# Sheet2.net
KiCad netlist of a schematic drawn in Altium Designer
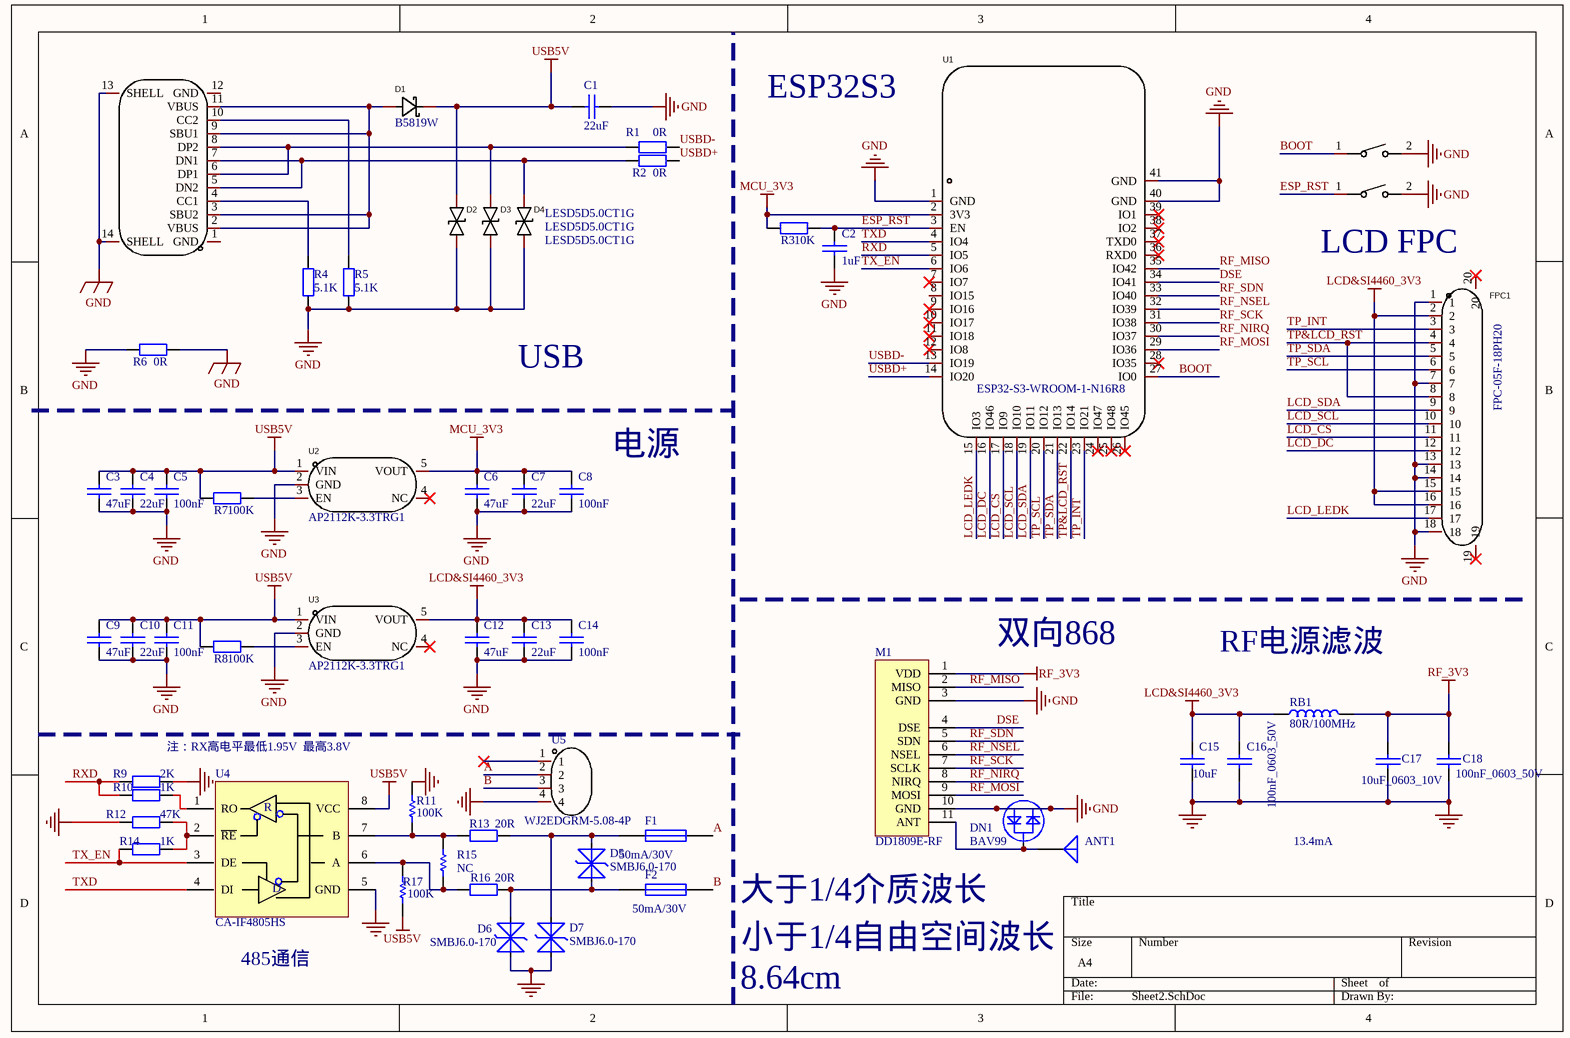
[diagram p0: Sheet2.SchDoc]

(export (version "E")
  (design (tool "Eeschema 10.0.6"))
  (components
    (comp (ref "ANT1")
      (value "~")
      (footprint "18AWG")
      (description "Generic Antenna")
      (fields (field (name "PUBLISHER") "Altium Limited"))
      (libsource (lib "原理图库") (part "Antenna"))
    )
    (comp (ref "C1")
      (value "22uF")
      (footprint "0603_C")
      (description "贴片电容")
      (libsource (lib "Schlib1") (part "CAP_SMT"))
    )
    (comp (ref "C2")
      (value "1uF")
      (footprint "0603_C")
      (description "贴片电容")
      (libsource (lib "Schlib1") (part "CAP_SMT"))
    )
    (comp (ref "C3")
      (value "47uF")
      (footprint "0603_C")
      (description "贴片电容")
      (libsource (lib "Schlib1") (part "CAP_SMT"))
    )
    (comp (ref "C4")
      (value "22uF")
      (footprint "0603_C")
      (description "贴片电容")
      (libsource (lib "Schlib1") (part "CAP_SMT"))
    )
    (comp (ref "C5")
      (value "100nF")
      (footprint "0603_C")
      (description "贴片电容")
      (libsource (lib "Schlib1") (part "CAP_SMT"))
    )
    (comp (ref "C6")
      (value "47uF")
      (footprint "0603_C")
      (description "贴片电容")
      (libsource (lib "Schlib1") (part "CAP_SMT"))
    )
    (comp (ref "C7")
      (value "22uF")
      (footprint "0603_C")
      (description "贴片电容")
      (libsource (lib "Schlib1") (part "CAP_SMT"))
    )
    (comp (ref "C8")
      (value "100nF")
      (footprint "0603_C")
      (description "贴片电容")
      (libsource (lib "Schlib1") (part "CAP_SMT"))
    )
    (comp (ref "C9")
      (value "47uF")
      (footprint "0603_C")
      (description "贴片电容")
      (libsource (lib "Schlib1") (part "CAP_SMT"))
    )
    (comp (ref "C10")
      (value "22uF")
      (footprint "0603_C")
      (description "贴片电容")
      (libsource (lib "Schlib1") (part "CAP_SMT"))
    )
    (comp (ref "C11")
      (value "100nF")
      (footprint "0603_C")
      (description "贴片电容")
      (libsource (lib "Schlib1") (part "CAP_SMT"))
    )
    (comp (ref "C12")
      (value "47uF")
      (footprint "0603_C")
      (description "贴片电容")
      (libsource (lib "Schlib1") (part "CAP_SMT"))
    )
    (comp (ref "C13")
      (value "22uF")
      (footprint "0603_C")
      (description "贴片电容")
      (libsource (lib "Schlib1") (part "CAP_SMT"))
    )
    (comp (ref "C14")
      (value "100nF")
      (footprint "0603_C")
      (description "贴片电容")
      (libsource (lib "Schlib1") (part "CAP_SMT"))
    )
    (comp (ref "C15")
      (value "10uF")
      (footprint "0603_C")
      (description "瓷片电容 X5R-0603-10V-10uF/C-±10%")
      (fields (field (name "Comment") "10uF_0603_10V"))
      (libsource (lib "mine") (part "10uF_0603_10V"))
    )
    (comp (ref "C16")
      (value "100nF_0603_50V")
      (footprint "0603_C")
      (description "电容 瓷片 X7R-0603-50V-0.1uF/C-±10%")
      (libsource (lib "mine") (part "100nF_0603_50V"))
    )
    (comp (ref "C17")
      (value "10uF_0603_10V")
      (footprint "0603_C")
      (description "瓷片电容 X5R-0603-10V-10uF/C-±10%")
      (libsource (lib "mine") (part "10uF_0603_10V"))
    )
    (comp (ref "C18")
      (value "100nF_0603_50V")
      (footprint "0603_C")
      (description "电容 瓷片 X7R-0603-50V-0.1uF/C-±10%")
      (libsource (lib "mine") (part "100nF_0603_50V"))
    )
    (comp (ref "D1")
      (value "B5819W")
      (footprint "SOD-123F_L2.7-W1.6-LS3.8-RD-1")
      (fields (field (name "MANUFACTURER") "GOODWORK(固得沃克)"))
      (libsource (lib "Schlib1") (part "B5819W"))
    )
    (comp (ref "D2")
      (value "LESD5D5.0CT1G")
      (footprint "SOD-523_L1.2-W0.8-LS1.6-BI")
      (fields (field (name "MANUFACTURER") "LRC(乐山无线电)"))
      (libsource (lib "Schlib1") (part "LESD5D5.0CT1G"))
    )
    (comp (ref "D3")
      (value "LESD5D5.0CT1G")
      (footprint "SOD-523_L1.2-W0.8-LS1.6-BI")
      (fields (field (name "MANUFACTURER") "LRC(乐山无线电)"))
      (libsource (lib "Schlib1") (part "LESD5D5.0CT1G"))
    )
    (comp (ref "D4")
      (value "LESD5D5.0CT1G")
      (footprint "SOD-523_L1.2-W0.8-LS1.6-BI")
      (fields (field (name "MANUFACTURER") "LRC(乐山无线电)"))
      (libsource (lib "Schlib1") (part "LESD5D5.0CT1G"))
    )
    (comp (ref "D5")
      (value "SMBJ6.0-170")
      (footprint "SMB(DO-214AA) - TVS")
      (description "TVS")
      (libsource (lib "Schlib1") (part "TVS"))
    )
    (comp (ref "D6")
      (value "SMBJ6.0-170")
      (footprint "SMB(DO-214AA) - TVS")
      (description "TVS")
      (libsource (lib "Schlib1") (part "TVS"))
    )
    (comp (ref "D7")
      (value "SMBJ6.0-170")
      (footprint "SMB(DO-214AA) - TVS")
      (description "TVS")
      (libsource (lib "Schlib1") (part "TVS"))
    )
    (comp (ref "DN1") (value "BAV99") (footprint "SOT-23(SOT-23-3)") (libsource (lib "Ruan") (part "BAV99")))
    (comp (ref "F1")
      (value "贴片自恢复保险丝 1812 0.1A 60V")
      (footprint "1206_R")
      (description "Fuse")
      (fields (field (name "ALTIUM_UNNAMED_1") "50mA/30V") (field (name "PUBLISHER") "Altium Limited"))
      (libsource (lib "*") (part "Fuse 1"))
    )
    (comp (ref "F2")
      (value "贴片自恢复保险丝 1812 0.1A 60V")
      (footprint "1206_R")
      (description "Fuse")
      (fields (field (name "ALTIUM_UNNAMED_1") "50mA/30V") (field (name "PUBLISHER") "Altium Limited"))
      (libsource (lib "*") (part "Fuse 1"))
    )
    (comp (ref "FPC1")
      (value "FPC-05F-18PH20")
      (footprint "FPC-SMD_18P-P0.50_FPC-05F-18PH20")
      (fields (field (name "MANUFACTURER") "XUNPU(讯普)"))
      (libsource (lib "Schlib1") (part "FPC-05F-18PH20"))
    )
    (comp (ref "M1")
      (value "DD1809E-RF")
      (footprint "DD1809(E)-RF-平")
      (description "平插")
      (libsource (lib "Ruan") (part "DD1809E-RF"))
    )
    (comp (ref "R1")
      (value "0R")
      (footprint "0603_R")
      (description "Resistor")
      (fields (field (name "PUBLISHER") "Altium Limited"))
      (libsource (lib "Schlib1") (part "RES"))
    )
    (comp (ref "R2")
      (value "0R")
      (footprint "0603_R")
      (description "Resistor")
      (fields (field (name "PUBLISHER") "Altium Limited"))
      (libsource (lib "Schlib1") (part "RES"))
    )
    (comp (ref "R3")
      (value "10K")
      (footprint "0603_R")
      (description "Resistor")
      (fields (field (name "Comment") "0R") (field (name "PUBLISHER") "Altium Limited"))
      (libsource (lib "Schlib1") (part "RES"))
    )
    (comp (ref "R4")
      (value "5.1K")
      (footprint "0603_R")
      (description "Resistor")
      (fields (field (name "PUBLISHER") "Altium Limited"))
      (libsource (lib "") (part "RES_1"))
    )
    (comp (ref "R5")
      (value "5.1K")
      (footprint "0603_R")
      (description "Resistor")
      (fields (field (name "PUBLISHER") "Altium Limited"))
      (libsource (lib "") (part "RES_1"))
    )
    (comp (ref "R6")
      (value "0R")
      (footprint "0603_R")
      (description "Resistor")
      (fields (field (name "PUBLISHER") "Altium Limited"))
      (libsource (lib "Schlib1") (part "RES"))
    )
    (comp (ref "R7")
      (value "100K")
      (footprint "0603_R")
      (description "Resistor")
      (fields (field (name "PUBLISHER") "Altium Limited"))
      (libsource (lib "Schlib1") (part "RES"))
    )
    (comp (ref "R8")
      (value "100K")
      (footprint "0603_R")
      (description "Resistor")
      (fields (field (name "PUBLISHER") "Altium Limited"))
      (libsource (lib "Schlib1") (part "RES"))
    )
    (comp (ref "R9")
      (value "2K")
      (footprint "0603_R")
      (description "Resistor")
      (fields (field (name "PUBLISHER") "Altium Limited"))
      (libsource (lib "") (part "Res2_2"))
    )
    (comp (ref "R10")
      (value "1K")
      (footprint "0603_R")
      (description "Resistor")
      (fields (field (name "PUBLISHER") "Altium Limited"))
      (libsource (lib "") (part "Res2_1"))
    )
    (comp (ref "R11")
      (value "100K")
      (footprint "0603_R")
      (description "Resistor")
      (fields (field (name "PUBLISHER") "Altium Limited"))
      (libsource (lib "*") (part "Res1"))
    )
    (comp (ref "R12")
      (value "47K")
      (footprint "0603_R")
      (description "Resistor")
      (fields (field (name "PUBLISHER") "Altium Limited"))
      (libsource (lib "") (part "Res2_1"))
    )
    (comp (ref "R13")
      (value "20R")
      (footprint "0603_R")
      (description "Resistor")
      (fields (field (name "PUBLISHER") "Altium Limited"))
      (libsource (lib "*") (part "Res2"))
    )
    (comp (ref "R14")
      (value "1K")
      (footprint "0603_R")
      (description "Resistor")
      (fields (field (name "PUBLISHER") "Altium Limited"))
      (libsource (lib "") (part "Res2_1"))
    )
    (comp (ref "R15")
      (value "NC")
      (footprint "0603_R")
      (description "Resistor")
      (fields (field (name "PUBLISHER") "Altium Limited"))
      (libsource (lib "*") (part "Res1"))
    )
    (comp (ref "R16")
      (value "20R")
      (footprint "0603_R")
      (description "Resistor")
      (fields (field (name "PUBLISHER") "Altium Limited"))
      (libsource (lib "*") (part "Res2"))
    )
    (comp (ref "R17")
      (value "100K")
      (footprint "0603_R")
      (description "Resistor")
      (fields (field (name "PUBLISHER") "Altium Limited"))
      (libsource (lib "*") (part "Res1"))
    )
    (comp (ref "RB1")
      (value "80R/100MHz")
      (footprint "0603_R")
      (description "磁珠 80R/100MHZ 贴片0603")
      (fields (field (name "Comment") "80R/100MHz_0603"))
      (libsource (lib "mine") (part "80R/100MHz_0603"))
    )
    (comp (ref "SW1")
      (value "TS-1088-AR02016")
      (footprint "SW-SMD_L3.9-W3.0-P4.45")
      (fields (field (name "MANUFACTURER") "XUNPU(讯普)"))
      (libsource (lib "Schlib1") (part "KEY"))
    )
    (comp (ref "SW2")
      (value "TS-1088-AR02016")
      (footprint "SW-SMD_L3.9-W3.0-P4.45")
      (fields (field (name "MANUFACTURER") "XUNPU(讯普)"))
      (libsource (lib "Schlib1") (part "KEY"))
    )
    (comp (ref "U1")
      (value "ESP32-S3-WROOM-1-N16R8")
      (footprint "WIRELM-SMD_ESP32-S3-WROOM-1")
      (fields (field (name "MANUFACTURER") "ESPRESSIF(乐鑫)"))
      (libsource (lib "Schlib1") (part "ESP32-S3-WROOM-1-N16R8"))
    )
    (comp (ref "U2")
      (value "AP2112K-3.3TRG1")
      (footprint "SOT-25-5_L2.9-W1.6-P0.95-LS2.8-BL")
      (fields (field (name "MANUFACTURER") "DIODES(美台)"))
      (libsource (lib "Schlib1") (part "AP2112K-3.3TRG1"))
    )
    (comp (ref "U3")
      (value "AP2112K-3.3TRG1")
      (footprint "SOT-25-5_L2.9-W1.6-P0.95-LS2.8-BL")
      (fields (field (name "MANUFACTURER") "DIODES(美台)"))
      (libsource (lib "Schlib1") (part "AP2112K-3.3TRG1"))
    )
    (comp (ref "U4")
      (value "CA-IF4805HS")
      (footprint "SOP8")
      (description "MAX485E")
      (libsource (lib "N IC-GRC") (part "MAX485E"))
    )
    (comp (ref "U5")
      (value "WJ2EDGRM-5.08-4P")
      (footprint "CONN-TH_4P-P5.08_WJ2EDGRM-5.08-4P-14-00A")
      (description "连接器类型:板端/插座-闭口;间距:5.08mm;排数:1;每排PIN数:4;安装方式:弯针;颜色:绿色;固定方式:螺丝固定;")
      (fields (field (name "MANUFACTURER") "KANGNEX(康奈克斯电气)") (field (name "NAME") "WJ2EDGRM-5.08-4P"))
      (libsource (lib "Schlib1") (part "WJ2EDGRM-5.08-4P"))
    )
    (comp (ref "USB1")
      (value "TYPE-C 16PIN 2MD(073)")
      (footprint "USB-C-SMD_TYPE-C-6PIN-2MD-073")
      (fields (field (name "MANUFACTURER") "SHOU HAN(首韩)"))
      (libsource (lib "Schlib1") (part "TYPE-C 16PIN 2MD(073)"))
    )
  )
  (nets
    (net (code "1") (name "/A") (class "Default")
      (node (ref "F1") (pin "2") (pinfunction "2_2") (pintype "passive"))
      (node (ref "U5") (pin "2") (pinfunction "2_2") (pintype "passive"))
    )
    (net (code "2") (name "/B") (class "Default")
      (node (ref "F2") (pin "2") (pinfunction "2_2") (pintype "passive"))
      (node (ref "U5") (pin "3") (pinfunction "3_3") (pintype "passive"))
    )
    (net (code "3") (name "/BOOT") (class "Default")
      (node (ref "SW1") (pin "1") (pinfunction "1_1") (pintype "passive"))
      (node (ref "U1") (pin "27") (pinfunction "IO0_27") (pintype "passive"))
    )
    (net (code "4") (name "/DSE") (class "Default")
      (node (ref "M1") (pin "4") (pinfunction "DSE_4") (pintype "passive"))
      (node (ref "U1") (pin "34") (pinfunction "IO41_34") (pintype "passive"))
    )
    (net (code "5") (name "/ESP_RST") (class "Default")
      (node (ref "C2") (pin "2") (pinfunction "2_2") (pintype "passive"))
      (node (ref "R3") (pin "2") (pinfunction "2_2") (pintype "passive"))
      (node (ref "SW2") (pin "1") (pinfunction "1_1") (pintype "passive"))
      (node (ref "U1") (pin "3") (pinfunction "EN_3") (pintype "passive"))
    )
    (net (code "6") (name "/LCD_CS") (class "Default")
      (node (ref "FPC1") (pin "11") (pinfunction "11_11") (pintype "passive"))
      (node (ref "U1") (pin "17") (pinfunction "IO9_17") (pintype "passive"))
    )
    (net (code "7") (name "/LCD_DC") (class "Default")
      (node (ref "FPC1") (pin "12") (pinfunction "12_12") (pintype "passive"))
      (node (ref "U1") (pin "16") (pinfunction "IO46_16") (pintype "passive"))
    )
    (net (code "8") (name "/LCD_LEDK") (class "Default")
      (node (ref "FPC1") (pin "17") (pinfunction "17_17") (pintype "passive"))
      (node (ref "U1") (pin "15") (pinfunction "IO3_15") (pintype "passive"))
    )
    (net (code "9") (name "/LCD_SCL") (class "Default")
      (node (ref "FPC1") (pin "10") (pinfunction "10_10") (pintype "passive"))
      (node (ref "U1") (pin "18") (pinfunction "IO10_18") (pintype "passive"))
    )
    (net (code "10") (name "/LCD_SDA") (class "Default")
      (node (ref "FPC1") (pin "9") (pinfunction "9_9") (pintype "passive"))
      (node (ref "U1") (pin "19") (pinfunction "IO11_19") (pintype "passive"))
    )
    (net (code "11") (name "/RF_MISO") (class "Default")
      (node (ref "M1") (pin "2") (pinfunction "MISO_2") (pintype "passive"))
      (node (ref "U1") (pin "35") (pinfunction "IO42_35") (pintype "passive"))
    )
    (net (code "12") (name "/RF_MOSI") (class "Default")
      (node (ref "M1") (pin "9") (pinfunction "MOSI_9") (pintype "passive"))
      (node (ref "U1") (pin "29") (pinfunction "IO36_29") (pintype "passive"))
    )
    (net (code "13") (name "/RF_NIRQ") (class "Default")
      (node (ref "M1") (pin "8") (pinfunction "NIRQ_8") (pintype "passive"))
      (node (ref "U1") (pin "30") (pinfunction "IO37_30") (pintype "passive"))
    )
    (net (code "14") (name "/RF_NSEL") (class "Default")
      (node (ref "M1") (pin "6") (pinfunction "NSEL_6") (pintype "passive"))
      (node (ref "U1") (pin "32") (pinfunction "IO39_32") (pintype "passive"))
    )
    (net (code "15") (name "/RF_SCK") (class "Default")
      (node (ref "M1") (pin "7") (pinfunction "SCLK_7") (pintype "passive"))
      (node (ref "U1") (pin "31") (pinfunction "IO38_31") (pintype "passive"))
    )
    (net (code "16") (name "/RF_SDN") (class "Default")
      (node (ref "M1") (pin "5") (pinfunction "SDN_5") (pintype "passive"))
      (node (ref "U1") (pin "33") (pinfunction "IO40_33") (pintype "passive"))
    )
    (net (code "17") (name "/RXD") (class "Default")
      (node (ref "R10") (pin "1") (pinfunction "1_1") (pintype "passive"))
      (node (ref "R9") (pin "2") (pinfunction "2_2") (pintype "passive"))
      (node (ref "U1") (pin "5") (pinfunction "IO5_5") (pintype "passive"))
    )
    (net (code "18") (name "/TP&LCD_RST") (class "Default")
      (node (ref "FPC1") (pin "4") (pinfunction "4_4") (pintype "passive"))
      (node (ref "FPC1") (pin "8") (pinfunction "8_8") (pintype "passive"))
      (node (ref "U1") (pin "22") (pinfunction "IO14_22") (pintype "passive"))
    )
    (net (code "19") (name "/TP_INT") (class "Default")
      (node (ref "FPC1") (pin "3") (pinfunction "3_3") (pintype "passive"))
      (node (ref "U1") (pin "23") (pinfunction "IO21_23") (pintype "passive"))
    )
    (net (code "20") (name "/TP_SCL") (class "Default")
      (node (ref "FPC1") (pin "6") (pinfunction "6_6") (pintype "passive"))
      (node (ref "U1") (pin "20") (pinfunction "IO12_20") (pintype "passive"))
    )
    (net (code "21") (name "/TP_SDA") (class "Default")
      (node (ref "FPC1") (pin "5") (pinfunction "5_5") (pintype "passive"))
      (node (ref "U1") (pin "21") (pinfunction "IO13_21") (pintype "passive"))
    )
    (net (code "22") (name "/TXD") (class "Default")
      (node (ref "U1") (pin "4") (pinfunction "IO4_4") (pintype "passive"))
      (node (ref "U4") (pin "4") (pinfunction "DI_4") (pintype "passive"))
    )
    (net (code "23") (name "/TX_EN") (class "Default")
      (node (ref "R14") (pin "1") (pinfunction "1_1") (pintype "passive"))
      (node (ref "U1") (pin "6") (pinfunction "IO6_6") (pintype "passive"))
      (node (ref "U4") (pin "3") (pinfunction "DE_3") (pintype "passive"))
    )
    (net (code "24") (name "/USBD+") (class "Default")
      (node (ref "R2") (pin "2") (pinfunction "2_2") (pintype "passive"))
      (node (ref "U1") (pin "14") (pinfunction "IO20_14") (pintype "passive"))
    )
    (net (code "25") (name "/USBD-") (class "Default")
      (node (ref "R1") (pin "2") (pinfunction "2_2") (pintype "passive"))
      (node (ref "U1") (pin "13") (pinfunction "IO19_13") (pintype "passive"))
    )
    (net (code "26") (name "GND") (class "Default")
      (node (ref "C1") (pin "2") (pinfunction "2_2") (pintype "passive"))
      (node (ref "C10") (pin "1") (pinfunction "1_1") (pintype "passive"))
      (node (ref "C11") (pin "1") (pinfunction "1_1") (pintype "passive"))
      (node (ref "C12") (pin "1") (pinfunction "1_1") (pintype "passive"))
      (node (ref "C13") (pin "1") (pinfunction "1_1") (pintype "passive"))
      (node (ref "C14") (pin "1") (pinfunction "1_1") (pintype "passive"))
      (node (ref "C15") (pin "2") (pinfunction "2_2") (pintype "passive"))
      (node (ref "C16") (pin "1") (pinfunction "1_1") (pintype "passive"))
      (node (ref "C17") (pin "1") (pinfunction "1_1") (pintype "passive"))
      (node (ref "C18") (pin "1") (pinfunction "1_1") (pintype "passive"))
      (node (ref "C2") (pin "1") (pinfunction "1_1") (pintype "passive"))
      (node (ref "C3") (pin "1") (pinfunction "1_1") (pintype "passive"))
      (node (ref "C4") (pin "1") (pinfunction "1_1") (pintype "passive"))
      (node (ref "C5") (pin "1") (pinfunction "1_1") (pintype "passive"))
      (node (ref "C6") (pin "1") (pinfunction "1_1") (pintype "passive"))
      (node (ref "C7") (pin "1") (pinfunction "1_1") (pintype "passive"))
      (node (ref "C8") (pin "1") (pinfunction "1_1") (pintype "passive"))
      (node (ref "C9") (pin "1") (pinfunction "1_1") (pintype "passive"))
      (node (ref "D2") (pin "1") (pinfunction "1_1") (pintype "passive"))
      (node (ref "D3") (pin "1") (pinfunction "1_1") (pintype "passive"))
      (node (ref "D4") (pin "1") (pinfunction "1_1") (pintype "passive"))
      (node (ref "D6") (pin "1") (pinfunction "1_1") (pintype "passive"))
      (node (ref "D7") (pin "1") (pinfunction "1_1") (pintype "passive"))
      (node (ref "DN1") (pin "1") (pinfunction "1_1") (pintype "passive"))
      (node (ref "DN1") (pin "2") (pinfunction "2_2") (pintype "passive"))
      (node (ref "FPC1") (pin "1") (pinfunction "1_1") (pintype "passive"))
      (node (ref "FPC1") (pin "13") (pinfunction "13_13") (pintype "passive"))
      (node (ref "FPC1") (pin "14") (pinfunction "14_14") (pintype "passive"))
      (node (ref "FPC1") (pin "18") (pinfunction "18_18") (pintype "passive"))
      (node (ref "FPC1") (pin "7") (pinfunction "7_7") (pintype "passive"))
      (node (ref "M1") (pin "10") (pinfunction "GND_10") (pintype "passive"))
      (node (ref "M1") (pin "3") (pinfunction "GND_3") (pintype "passive"))
      (node (ref "R11") (pin "2") (pinfunction "2_2") (pintype "passive"))
      (node (ref "R12") (pin "1") (pinfunction "1_1") (pintype "passive"))
      (node (ref "R4") (pin "1") (pinfunction "1_1") (pintype "passive"))
      (node (ref "R5") (pin "1") (pinfunction "1_1") (pintype "passive"))
      (node (ref "R6") (pin "1") (pinfunction "1_1") (pintype "passive"))
      (node (ref "R6") (pin "2") (pinfunction "2_2") (pintype "passive"))
      (node (ref "R9") (pin "1") (pinfunction "1_1") (pintype "passive"))
      (node (ref "SW1") (pin "2") (pinfunction "2_2") (pintype "passive"))
      (node (ref "SW2") (pin "2") (pinfunction "2_2") (pintype "passive"))
      (node (ref "U1") (pin "1") (pinfunction "GND_1") (pintype "passive"))
      (node (ref "U1") (pin "40") (pinfunction "GND_40") (pintype "passive"))
      (node (ref "U1") (pin "41") (pinfunction "GND_41") (pintype "passive"))
      (node (ref "U2") (pin "2") (pinfunction "GND_2") (pintype "passive"))
      (node (ref "U3") (pin "2") (pinfunction "GND_2") (pintype "passive"))
      (node (ref "U4") (pin "5") (pinfunction "GND_5") (pintype "passive"))
      (node (ref "U5") (pin "4") (pinfunction "4_4") (pintype "passive"))
      (node (ref "USB1") (pin "13") (pinfunction "SHELL_13") (pintype "passive"))
      (node (ref "USB1") (pin "14") (pinfunction "SHELL_14") (pintype "passive"))
    )
    (net (code "27") (name "LCD&SI4460_3V3") (class "Default")
      (node (ref "C12") (pin "2") (pinfunction "2_2") (pintype "passive"))
      (node (ref "C13") (pin "2") (pinfunction "2_2") (pintype "passive"))
      (node (ref "C14") (pin "2") (pinfunction "2_2") (pintype "passive"))
      (node (ref "C15") (pin "1") (pinfunction "1_1") (pintype "passive"))
      (node (ref "C16") (pin "2") (pinfunction "2_2") (pintype "passive"))
      (node (ref "FPC1") (pin "15") (pinfunction "15_15") (pintype "passive"))
      (node (ref "FPC1") (pin "16") (pinfunction "16_16") (pintype "passive"))
      (node (ref "FPC1") (pin "2") (pinfunction "2_2") (pintype "passive"))
      (node (ref "RB1") (pin "1") (pinfunction "1_1") (pintype "passive"))
      (node (ref "U3") (pin "5") (pinfunction "VOUT_5") (pintype "passive"))
    )
    (net (code "28") (name "MCU_3V3") (class "Default")
      (node (ref "C6") (pin "2") (pinfunction "2_2") (pintype "passive"))
      (node (ref "C7") (pin "2") (pinfunction "2_2") (pintype "passive"))
      (node (ref "C8") (pin "2") (pinfunction "2_2") (pintype "passive"))
      (node (ref "R3") (pin "1") (pinfunction "1_1") (pintype "passive"))
      (node (ref "U1") (pin "2") (pinfunction "3V3_2") (pintype "passive"))
      (node (ref "U2") (pin "5") (pinfunction "VOUT_5") (pintype "passive"))
    )
    (net (code "29") (name "Net-(ANT1-A)") (class "Default")
      (node (ref "ANT1") (pin "1") (pinfunction "A_1") (pintype "passive"))
      (node (ref "DN1") (pin "3") (pinfunction "3_3") (pintype "passive"))
      (node (ref "M1") (pin "11") (pinfunction "ANT_11") (pintype "passive"))
    )
    (net (code "30") (name "Net-(D1-A)") (class "Default")
      (node (ref "D1") (pin "2") (pinfunction "A_2") (pintype "passive"))
      (node (ref "USB1") (pin "11") (pinfunction "VBUS_11") (pintype "passive"))
      (node (ref "USB1") (pin "2") (pinfunction "VBUS_2") (pintype "passive"))
      (node (ref "USB1") (pin "3") (pinfunction "SBU2_3") (pintype "passive"))
      (node (ref "USB1") (pin "9") (pinfunction "SBU1_9") (pintype "passive"))
    )
    (net (code "31") (name "Net-(D5-Pad1)") (class "Default")
      (node (ref "D5") (pin "1") (pinfunction "1_1") (pintype "passive"))
      (node (ref "D6") (pin "2") (pinfunction "2_2") (pintype "passive"))
      (node (ref "F2") (pin "1") (pinfunction "1_1") (pintype "passive"))
      (node (ref "R16") (pin "1") (pinfunction "1_1") (pintype "passive"))
    )
    (net (code "32") (name "Net-(D5-Pad2)") (class "Default")
      (node (ref "D5") (pin "2") (pinfunction "2_2") (pintype "passive"))
      (node (ref "D7") (pin "2") (pinfunction "2_2") (pintype "passive"))
      (node (ref "F1") (pin "1") (pinfunction "1_1") (pintype "passive"))
      (node (ref "R13") (pin "1") (pinfunction "1_1") (pintype "passive"))
    )
    (net (code "33") (name "Net-(U2-EN)") (class "Default")
      (node (ref "R7") (pin "2") (pinfunction "2_2") (pintype "passive"))
      (node (ref "U2") (pin "3") (pinfunction "EN_3") (pintype "passive"))
    )
    (net (code "34") (name "Net-(U3-EN)") (class "Default")
      (node (ref "R8") (pin "2") (pinfunction "2_2") (pintype "passive"))
      (node (ref "U3") (pin "3") (pinfunction "EN_3") (pintype "passive"))
    )
    (net (code "35") (name "Net-(U4-A)") (class "Default")
      (node (ref "R15") (pin "1") (pinfunction "1_1") (pintype "passive"))
      (node (ref "R16") (pin "2") (pinfunction "2_2") (pintype "passive"))
      (node (ref "R17") (pin "2") (pinfunction "2_2") (pintype "passive"))
      (node (ref "U4") (pin "6") (pinfunction "A_6") (pintype "passive"))
    )
    (net (code "36") (name "Net-(U4-B)") (class "Default")
      (node (ref "R11") (pin "1") (pinfunction "1_1") (pintype "passive"))
      (node (ref "R13") (pin "2") (pinfunction "2_2") (pintype "passive"))
      (node (ref "R15") (pin "2") (pinfunction "2_2") (pintype "passive"))
      (node (ref "U4") (pin "7") (pinfunction "B_7") (pintype "passive"))
    )
    (net (code "37") (name "Net-(U4-RO)") (class "Default")
      (node (ref "R10") (pin "2") (pinfunction "2_2") (pintype "passive"))
      (node (ref "U4") (pin "1") (pinfunction "RO_1") (pintype "passive"))
    )
    (net (code "38") (name "Net-(U4-~{RE})") (class "Default")
      (node (ref "R12") (pin "2") (pinfunction "2_2") (pintype "passive"))
      (node (ref "R14") (pin "2") (pinfunction "2_2") (pintype "passive"))
      (node (ref "U4") (pin "2") (pinfunction "~{RE}_2") (pintype "passive"))
    )
    (net (code "39") (name "Net-(USB1-CC1)") (class "Default")
      (node (ref "R4") (pin "2") (pinfunction "2_2") (pintype "passive"))
      (node (ref "USB1") (pin "4") (pinfunction "CC1_4") (pintype "passive"))
    )
    (net (code "40") (name "Net-(USB1-CC2)") (class "Default")
      (node (ref "R5") (pin "2") (pinfunction "2_2") (pintype "passive"))
      (node (ref "USB1") (pin "10") (pinfunction "CC2_10") (pintype "passive"))
    )
    (net (code "41") (name "Net-(USB1-DN1)") (class "Default")
      (node (ref "D4") (pin "2") (pinfunction "2_2") (pintype "passive"))
      (node (ref "R2") (pin "1") (pinfunction "1_1") (pintype "passive"))
      (node (ref "USB1") (pin "5") (pinfunction "DN2_5") (pintype "passive"))
      (node (ref "USB1") (pin "7") (pinfunction "DN1_7") (pintype "passive"))
    )
    (net (code "42") (name "Net-(USB1-DP1)") (class "Default")
      (node (ref "D3") (pin "2") (pinfunction "2_2") (pintype "passive"))
      (node (ref "R1") (pin "1") (pinfunction "1_1") (pintype "passive"))
      (node (ref "USB1") (pin "6") (pinfunction "DP1_6") (pintype "passive"))
      (node (ref "USB1") (pin "8") (pinfunction "DP2_8") (pintype "passive"))
    )
    (net (code "43") (name "RF_3V3") (class "Default")
      (node (ref "C17") (pin "2") (pinfunction "2_2") (pintype "passive"))
      (node (ref "C18") (pin "2") (pinfunction "2_2") (pintype "passive"))
      (node (ref "M1") (pin "1") (pinfunction "VDD_1") (pintype "passive"))
      (node (ref "RB1") (pin "2") (pinfunction "2_2") (pintype "passive"))
    )
    (net (code "44") (name "USB5V") (class "Default")
      (node (ref "C1") (pin "1") (pinfunction "1_1") (pintype "passive"))
      (node (ref "C10") (pin "2") (pinfunction "2_2") (pintype "passive"))
      (node (ref "C11") (pin "2") (pinfunction "2_2") (pintype "passive"))
      (node (ref "C3") (pin "2") (pinfunction "2_2") (pintype "passive"))
      (node (ref "C4") (pin "2") (pinfunction "2_2") (pintype "passive"))
      (node (ref "C5") (pin "2") (pinfunction "2_2") (pintype "passive"))
      (node (ref "C9") (pin "2") (pinfunction "2_2") (pintype "passive"))
      (node (ref "D1") (pin "1") (pinfunction "K_1") (pintype "passive"))
      (node (ref "D2") (pin "2") (pinfunction "2_2") (pintype "passive"))
      (node (ref "R17") (pin "1") (pinfunction "1_1") (pintype "passive"))
      (node (ref "R7") (pin "1") (pinfunction "1_1") (pintype "passive"))
      (node (ref "R8") (pin "1") (pinfunction "1_1") (pintype "passive"))
      (node (ref "U2") (pin "1") (pinfunction "VIN_1") (pintype "passive"))
      (node (ref "U3") (pin "1") (pinfunction "VIN_1") (pintype "passive"))
      (node (ref "U4") (pin "8") (pinfunction "VCC_8") (pintype "passive"))
    )
    (net (code "45") (name "unconnected-(FPC1-Pad19)") (class "Default")
      (node (ref "FPC1") (pin "19") (pinfunction "19_19") (pintype "passive+no_connect"))
    )
    (net (code "46") (name "unconnected-(FPC1-Pad20)") (class "Default")
      (node (ref "FPC1") (pin "20") (pinfunction "20_20") (pintype "passive+no_connect"))
    )
    (net (code "47") (name "unconnected-(U1-IO1-Pad39)") (class "Default")
      (node (ref "U1") (pin "39") (pinfunction "IO1_39") (pintype "passive+no_connect"))
    )
    (net (code "48") (name "unconnected-(U1-IO2-Pad38)") (class "Default")
      (node (ref "U1") (pin "38") (pinfunction "IO2_38") (pintype "passive+no_connect"))
    )
    (net (code "49") (name "unconnected-(U1-IO7-Pad7)") (class "Default")
      (node (ref "U1") (pin "7") (pinfunction "IO7_7") (pintype "passive+no_connect"))
    )
    (net (code "50") (name "unconnected-(U1-IO8-Pad12)") (class "Default")
      (node (ref "U1") (pin "12") (pinfunction "IO8_12") (pintype "passive+no_connect"))
    )
    (net (code "51") (name "unconnected-(U1-IO15-Pad8)") (class "Default")
      (node (ref "U1") (pin "8") (pinfunction "IO15_8") (pintype "passive"))
    )
    (net (code "52") (name "unconnected-(U1-IO16-Pad9)") (class "Default")
      (node (ref "U1") (pin "9") (pinfunction "IO16_9") (pintype "passive+no_connect"))
    )
    (net (code "53") (name "unconnected-(U1-IO17-Pad10)") (class "Default")
      (node (ref "U1") (pin "10") (pinfunction "IO17_10") (pintype "passive+no_connect"))
    )
    (net (code "54") (name "unconnected-(U1-IO18-Pad11)") (class "Default")
      (node (ref "U1") (pin "11") (pinfunction "IO18_11") (pintype "passive+no_connect"))
    )
    (net (code "55") (name "unconnected-(U1-IO35-Pad28)") (class "Default")
      (node (ref "U1") (pin "28") (pinfunction "IO35_28") (pintype "passive+no_connect"))
    )
    (net (code "56") (name "unconnected-(U1-IO45-Pad26)") (class "Default")
      (node (ref "U1") (pin "26") (pinfunction "IO45_26") (pintype "passive+no_connect"))
    )
    (net (code "57") (name "unconnected-(U1-IO47-Pad24)") (class "Default")
      (node (ref "U1") (pin "24") (pinfunction "IO47_24") (pintype "passive+no_connect"))
    )
    (net (code "58") (name "unconnected-(U1-IO48-Pad25)") (class "Default")
      (node (ref "U1") (pin "25") (pinfunction "IO48_25") (pintype "passive+no_connect"))
    )
    (net (code "59") (name "unconnected-(U1-RXD0-Pad36)") (class "Default")
      (node (ref "U1") (pin "36") (pinfunction "RXD0_36") (pintype "passive+no_connect"))
    )
    (net (code "60") (name "unconnected-(U1-TXD0-Pad37)") (class "Default")
      (node (ref "U1") (pin "37") (pinfunction "TXD0_37") (pintype "passive+no_connect"))
    )
    (net (code "61") (name "unconnected-(U2-NC-Pad4)") (class "Default")
      (node (ref "U2") (pin "4") (pinfunction "NC_4") (pintype "passive+no_connect"))
    )
    (net (code "62") (name "unconnected-(U3-NC-Pad4)") (class "Default")
      (node (ref "U3") (pin "4") (pinfunction "NC_4") (pintype "passive+no_connect"))
    )
    (net (code "63") (name "unconnected-(U5-Pad1)") (class "Default")
      (node (ref "U5") (pin "1") (pinfunction "1_1") (pintype "passive+no_connect"))
    )
    (net (code "64") (name "unconnected-(USB1-GND-Pad1)") (class "Default")
      (node (ref "USB1") (pin "1") (pinfunction "GND_1") (pintype "passive"))
    )
    (net (code "65") (name "unconnected-(USB1-GND-Pad12)") (class "Default")
      (node (ref "USB1") (pin "12") (pinfunction "GND_12") (pintype "passive"))
    )
  )
)
